# Adder.net
KiCad netlist of a schematic drawn in Altium Designer
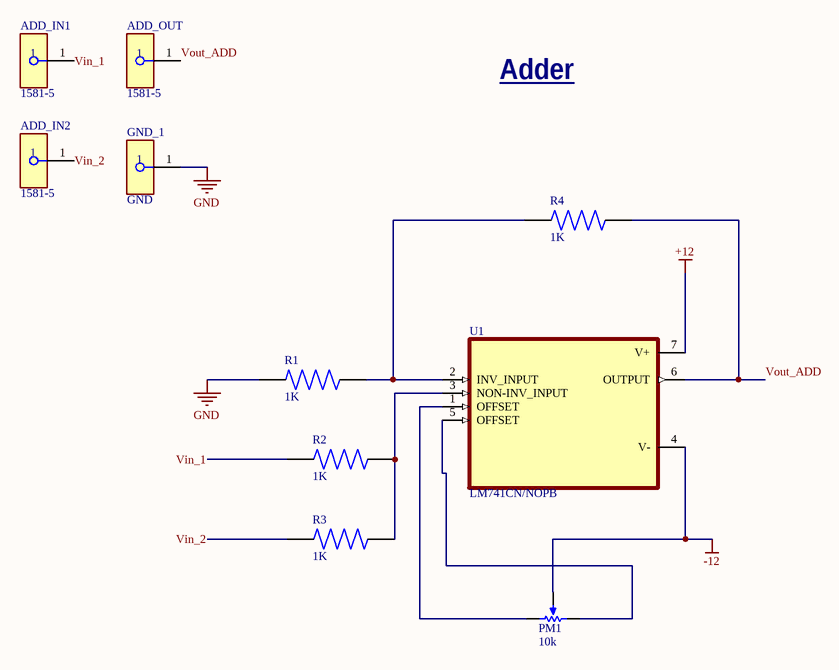
[diagram p0: Adder.SchDoc]

(export (version "E")
  (design (tool "Eeschema 10.0.6"))
  (components
    (comp (ref "ADD_IN1")
      (value "1581-5")
      (footprint "FP-1581-5-MFG")
      (description "CONN BANANA JACK TURRET GREEN")
      (libsource (lib "Altium Content Vault") (part "c5c826e0c4b67fe3b42ef77f2d4decc"))
    )
    (comp (ref "ADD_IN2")
      (value "1581-5")
      (footprint "FP-1581-5-MFG")
      (description "CONN BANANA JACK TURRET GREEN")
      (libsource (lib "Altium Content Vault") (part "c5c826e0c4b67fe3b42ef77f2d4decc"))
    )
    (comp (ref "ADD_OUT")
      (value "1581-5")
      (footprint "FP-1581-5-MFG")
      (description "CONN BANANA JACK TURRET GREEN")
      (libsource (lib "Altium Content Vault") (part "c5c826e0c4b67fe3b42ef77f2d4decc"))
    )
    (comp (ref "GND_1")
      (value "GND")
      (footprint "FP-1581-5-MFG")
      (description "CONN BANANA JACK TURRET GREEN")
      (libsource (lib "Altium Content Vault") (part "c5c826e0c4b67fe3b42ef77f2d4decc"))
    )
    (comp (ref "PM1")
      (value "10k")
      (footprint "BOUR-3362P")
      (description "Square Trimpot(R) Trimming Potentiometer, 10 KOhm, 300 V, -55 to 125 degC, 3-Pin THD, RoHS, Tube")
      (fields (field (name "TOLERANCE") "1%"))
      (libsource (lib "Altium Content Vault") (part "RES-POT-3"))
    )
    (comp (ref "R1")
      (value "1K")
      (footprint "RESAD1100W55L680D260")
      (description "1.07 kOhms Â±1% 0.25W, 1/4W Through Hole Resistor Axial - Metal Film")
      (fields (field (name "MF") "Yageo") (field (name "MP") "MFR-25FBF52-1K"))
      (libsource (lib "MFR-25FBF52-1K") (part "MFR-25FBF52-1K"))
    )
    (comp (ref "R2")
      (value "1K")
      (footprint "RESAD1100W55L680D260")
      (description "1.07 kOhms Â±1% 0.25W, 1/4W Through Hole Resistor Axial - Metal Film")
      (fields (field (name "MF") "Yageo") (field (name "MP") "MFR-25FBF52-1K"))
      (libsource (lib "MFR-25FBF52-1K") (part "MFR-25FBF52-1K"))
    )
    (comp (ref "R3")
      (value "1K")
      (footprint "RESAD1100W55L680D260")
      (description "1.07 kOhms Â±1% 0.25W, 1/4W Through Hole Resistor Axial - Metal Film")
      (fields (field (name "MF") "Yageo") (field (name "MP") "MFR-25FBF52-1K"))
      (libsource (lib "MFR-25FBF52-1K") (part "MFR-25FBF52-1K"))
    )
    (comp (ref "R4")
      (value "1K")
      (footprint "RESAD1100W55L680D260")
      (description "1.07 kOhms Â±1% 0.25W, 1/4W Through Hole Resistor Axial - Metal Film")
      (fields (field (name "MF") "Yageo") (field (name "MP") "MFR-25FBF52-1K"))
      (libsource (lib "MFR-25FBF52-1K") (part "MFR-25FBF52-1K"))
    )
    (comp (ref "U1")
      (value "LM741CN/NOPB")
      (footprint "DIP794W45P254L959H508Q8")
      (description "Single, 44-V, 1-MHz operational amplifier")
      (fields (field (name "MF") "Texas Instruments"))
      (libsource (lib "LM741CN_NOPB (1)") (part "LM741CN/NOPB"))
    )
  )
  (nets
    (net (code "1") (name "+12") (class "Default")
      (node (ref "U1") (pin "7") (pinfunction "V+_7") (pintype "power_in"))
    )
    (net (code "2") (name "-12") (class "Default")
      (node (ref "PM1") (pin "2") (pinfunction "S_2") (pintype "passive"))
      (node (ref "U1") (pin "4") (pinfunction "V-_4") (pintype "power_in"))
    )
    (net (code "3") (name "/Vin_1") (class "Default")
      (node (ref "ADD_IN1") (pin "1") (pinfunction "1_1") (pintype "passive"))
      (node (ref "R2") (pin "1") (pinfunction "1_1") (pintype "passive"))
    )
    (net (code "4") (name "/Vin_2") (class "Default")
      (node (ref "ADD_IN2") (pin "1") (pinfunction "1_1") (pintype "passive"))
      (node (ref "R3") (pin "1") (pinfunction "1_1") (pintype "passive"))
    )
    (net (code "5") (name "/Vout_ADD") (class "Default")
      (node (ref "ADD_OUT") (pin "1") (pinfunction "1_1") (pintype "passive"))
      (node (ref "R4") (pin "2") (pinfunction "2_2") (pintype "passive"))
      (node (ref "U1") (pin "6") (pinfunction "OUTPUT_6") (pintype "output"))
    )
    (net (code "6") (name "GND") (class "Default")
      (node (ref "GND_1") (pin "1") (pinfunction "1_1") (pintype "passive"))
      (node (ref "R1") (pin "1") (pinfunction "1_1") (pintype "passive"))
    )
    (net (code "7") (name "Net-(PM1-CCW)") (class "Default")
      (node (ref "PM1") (pin "1") (pinfunction "CCW_1") (pintype "passive"))
      (node (ref "U1") (pin "5") (pinfunction "OFFSET_5") (pintype "input"))
    )
    (net (code "8") (name "Net-(PM1-CW)") (class "Default")
      (node (ref "PM1") (pin "3") (pinfunction "CW_3") (pintype "passive"))
      (node (ref "U1") (pin "1") (pinfunction "OFFSET_1") (pintype "input"))
    )
    (net (code "9") (name "Net-(U1-INV_INPUT)") (class "Default")
      (node (ref "R1") (pin "2") (pinfunction "2_2") (pintype "passive"))
      (node (ref "R4") (pin "1") (pinfunction "1_1") (pintype "passive"))
      (node (ref "U1") (pin "2") (pinfunction "INV_INPUT_2") (pintype "input"))
    )
    (net (code "10") (name "Net-(U1-NON-INV_INPUT)") (class "Default")
      (node (ref "R2") (pin "2") (pinfunction "2_2") (pintype "passive"))
      (node (ref "R3") (pin "2") (pinfunction "2_2") (pintype "passive"))
      (node (ref "U1") (pin "3") (pinfunction "NON-INV_INPUT_3") (pintype "input"))
    )
  )
)
